# UI_Interface.net
KiCad netlist of a schematic drawn in Altium Designer
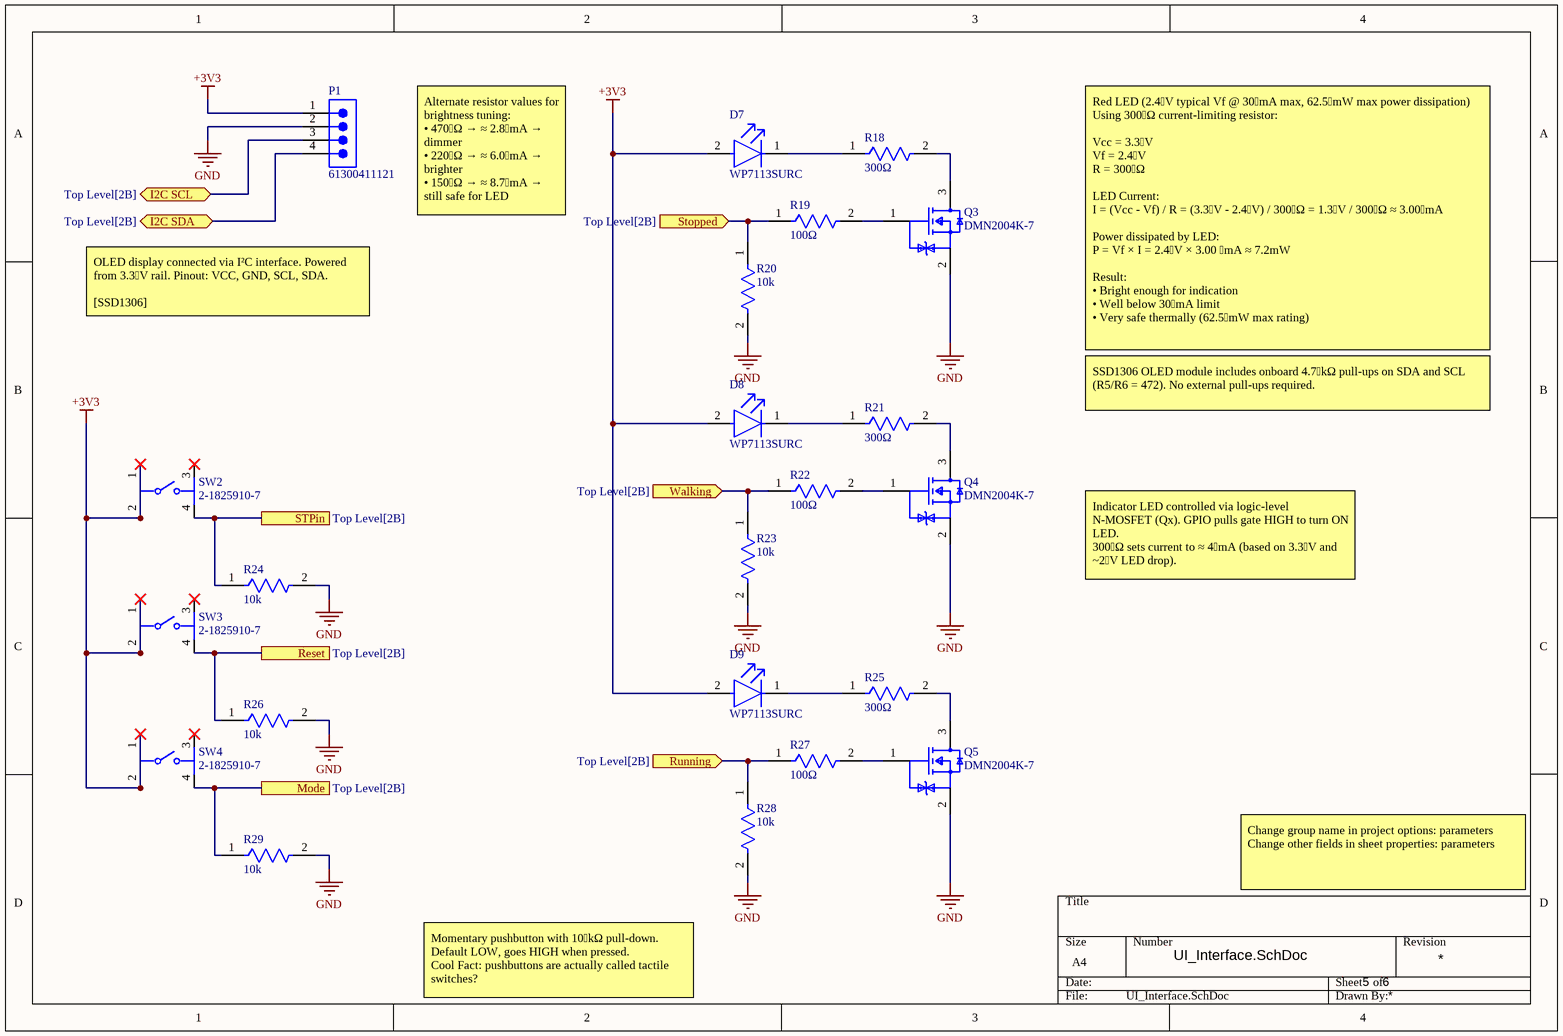
[diagram p0: UI_Interface.SchDoc]

(export (version "E")
  (design (tool "Eeschema 10.0.6"))
  (components
    (comp (ref "D7")
      (value "WP7113SURC")
      (footprint "FP-WP7113SURC-MFG")
      (description "WP7113SURC Red 5 mm 20 º Water Clear 3800 mcd 1.9 V Solid State LED Lamp - T-1 3/4")
      (libsource (lib "Altium Content Vault") (part "8706943c75ba83719d021d2fdc84c58"))
    )
    (comp (ref "D8")
      (value "WP7113SURC")
      (footprint "FP-WP7113SURC-MFG")
      (description "WP7113SURC Red 5 mm 20 º Water Clear 3800 mcd 1.9 V Solid State LED Lamp - T-1 3/4")
      (libsource (lib "Altium Content Vault") (part "8706943c75ba83719d021d2fdc84c58"))
    )
    (comp (ref "D9")
      (value "WP7113SURC")
      (footprint "FP-WP7113SURC-MFG")
      (description "WP7113SURC Red 5 mm 20 º Water Clear 3800 mcd 1.9 V Solid State LED Lamp - T-1 3/4")
      (libsource (lib "Altium Content Vault") (part "8706943c75ba83719d021d2fdc84c58"))
    )
    (comp (ref "P1")
      (value "61300411121")
      (footprint "61300411121")
      (libsource (lib "Altium Content Vault") (part "Header_Male_1R_04P"))
    )
    (comp (ref "Q3")
      (value "DMN2004K-7")
      (footprint "FP-SOT23-MFG")
      (description "MOSFET N-CH 20V 0.63A SOT23-3")
      (fields
        (field (name "OCTOPART") "https://octopart.com/dmn2004k-7-diodes+inc.-7127688")
        (field (name "MANUFACTURER") "Diodes Inc.")
      )
      (libsource (lib "Altium Content Vault") (part "6bf9a98fc5d989e2cd7172508213873"))
    )
    (comp (ref "Q4")
      (value "DMN2004K-7")
      (footprint "FP-SOT23-MFG")
      (description "MOSFET N-CH 20V 0.63A SOT23-3")
      (fields
        (field (name "OCTOPART") "https://octopart.com/dmn2004k-7-diodes+inc.-7127688")
        (field (name "MANUFACTURER") "Diodes Inc.")
      )
      (libsource (lib "Altium Content Vault") (part "6bf9a98fc5d989e2cd7172508213873"))
    )
    (comp (ref "Q5")
      (value "DMN2004K-7")
      (footprint "FP-SOT23-MFG")
      (description "MOSFET N-CH 20V 0.63A SOT23-3")
      (fields
        (field (name "OCTOPART") "https://octopart.com/dmn2004k-7-diodes+inc.-7127688")
        (field (name "MANUFACTURER") "Diodes Inc.")
      )
      (libsource (lib "Altium Content Vault") (part "6bf9a98fc5d989e2cd7172508213873"))
    )
    (comp (ref "R18")
      (value "300Ω")
      (footprint "FP-RMCF0805-IPC_B")
      (description "300Ω ±5% 0.125W 0805 Thick Film Chip Resistor AEC-Q200 compliant, RMCF0805JT300R")
      (fields (field (name "TOLERANCE") "5%"))
      (libsource (lib "Altium Content Vault") (part "1029c3af85768c4190bb7ad29bc67b5"))
    )
    (comp (ref "R19")
      (value "100Ω")
      (footprint "FP-RMCF0805-IPC_A")
      (description "100Ω ±1% 0.125W 0805 Thick Film Chip Resistor AEC-Q200 compliant, RMCF0805FT100R")
      (fields (field (name "TOLERANCE") "1%"))
      (libsource (lib "Altium Content Vault") (part "1029c3af85768c4190bb7ad29bc67b5"))
    )
    (comp (ref "R20")
      (value "10k")
      (footprint "FP-RMCF0805-MFG")
      (description "RES 10K OHM 1% 1/8W 0805, RMCF0805FT10K0")
      (fields (field (name "TOLERANCE") "1%"))
      (libsource (lib "Altium Content Vault") (part "1029c3af85768c4190bb7ad29bc67b5"))
    )
    (comp (ref "R21")
      (value "300Ω")
      (footprint "FP-RMCF0805-IPC_B")
      (description "300Ω ±5% 0.125W 0805 Thick Film Chip Resistor AEC-Q200 compliant, RMCF0805JT300R")
      (fields (field (name "TOLERANCE") "5%"))
      (libsource (lib "Altium Content Vault") (part "1029c3af85768c4190bb7ad29bc67b5"))
    )
    (comp (ref "R22")
      (value "100Ω")
      (footprint "FP-RMCF0805-IPC_A")
      (description "100Ω ±1% 0.125W 0805 Thick Film Chip Resistor AEC-Q200 compliant, RMCF0805FT100R")
      (fields (field (name "TOLERANCE") "1%"))
      (libsource (lib "Altium Content Vault") (part "1029c3af85768c4190bb7ad29bc67b5"))
    )
    (comp (ref "R23")
      (value "10k")
      (footprint "FP-RMCF0805-MFG")
      (description "RES 10K OHM 1% 1/8W 0805, RMCF0805FT10K0")
      (fields (field (name "TOLERANCE") "1%"))
      (libsource (lib "Altium Content Vault") (part "1029c3af85768c4190bb7ad29bc67b5"))
    )
    (comp (ref "R24")
      (value "10k")
      (footprint "FP-RMCF0805-MFG")
      (description "RES 10K OHM 1% 1/8W 0805, RMCF0805FT10K0")
      (fields (field (name "TOLERANCE") "1%"))
      (libsource (lib "Altium Content Vault") (part "1029c3af85768c4190bb7ad29bc67b5"))
    )
    (comp (ref "R25")
      (value "300Ω")
      (footprint "FP-RMCF0805-IPC_B")
      (description "300Ω ±5% 0.125W 0805 Thick Film Chip Resistor AEC-Q200 compliant, RMCF0805JT300R")
      (fields (field (name "TOLERANCE") "5%"))
      (libsource (lib "Altium Content Vault") (part "1029c3af85768c4190bb7ad29bc67b5"))
    )
    (comp (ref "R26")
      (value "10k")
      (footprint "FP-RMCF0805-MFG")
      (description "RES 10K OHM 1% 1/8W 0805, RMCF0805FT10K0")
      (fields (field (name "TOLERANCE") "1%"))
      (libsource (lib "Altium Content Vault") (part "1029c3af85768c4190bb7ad29bc67b5"))
    )
    (comp (ref "R27")
      (value "100Ω")
      (footprint "FP-RMCF0805-IPC_A")
      (description "100Ω ±1% 0.125W 0805 Thick Film Chip Resistor AEC-Q200 compliant, RMCF0805FT100R")
      (fields (field (name "TOLERANCE") "1%"))
      (libsource (lib "Altium Content Vault") (part "1029c3af85768c4190bb7ad29bc67b5"))
    )
    (comp (ref "R28")
      (value "10k")
      (footprint "FP-RMCF0805-MFG")
      (description "RES 10K OHM 1% 1/8W 0805, RMCF0805FT10K0")
      (fields (field (name "TOLERANCE") "1%"))
      (libsource (lib "Altium Content Vault") (part "1029c3af85768c4190bb7ad29bc67b5"))
    )
    (comp (ref "R29")
      (value "10k")
      (footprint "FP-RMCF0805-MFG")
      (description "RES 10K OHM 1% 1/8W 0805, RMCF0805FT10K0")
      (fields (field (name "TOLERANCE") "1%"))
      (libsource (lib "Altium Content Vault") (part "1029c3af85768c4190bb7ad29bc67b5"))
    )
    (comp (ref "SW2")
      (value "2-1825910-7")
      (footprint "FP-2-1825910-7-MFG")
      (description "SWITCH TACTILE SPST-NO 0.05A 24V")
      (fields
        (field (name "MANUFACTURER") "TE Connectivity")
        (field (name "OCTOPART") "https://octopart.com/2-1825910-7-te+connectivity-42270510")
      )
      (libsource (lib "Altium Content Vault") (part "b8895f3f4cefb76e1819d2863dba89b"))
    )
    (comp (ref "SW3")
      (value "2-1825910-7")
      (footprint "FP-2-1825910-7-MFG")
      (description "SWITCH TACTILE SPST-NO 0.05A 24V")
      (fields
        (field (name "MANUFACTURER") "TE Connectivity")
        (field (name "OCTOPART") "https://octopart.com/2-1825910-7-te+connectivity-42270510")
      )
      (libsource (lib "Altium Content Vault") (part "b8895f3f4cefb76e1819d2863dba89b"))
    )
    (comp (ref "SW4")
      (value "2-1825910-7")
      (footprint "FP-2-1825910-7-MFG")
      (description "SWITCH TACTILE SPST-NO 0.05A 24V")
      (fields
        (field (name "MANUFACTURER") "TE Connectivity")
        (field (name "OCTOPART") "https://octopart.com/2-1825910-7-te+connectivity-42270510")
      )
      (libsource (lib "Altium Content Vault") (part "b8895f3f4cefb76e1819d2863dba89b"))
    )
  )
  (nets
    (net (code "1") (name "+3V3") (class "Default")
      (node (ref "D7") (pin "2") (pinfunction "A_2") (pintype "passive"))
      (node (ref "D8") (pin "2") (pinfunction "A_2") (pintype "passive"))
      (node (ref "D9") (pin "2") (pinfunction "A_2") (pintype "passive"))
      (node (ref "P1") (pin "1") (pinfunction "1_1") (pintype "passive"))
      (node (ref "SW2") (pin "1") (pinfunction "1_1") (pintype "passive"))
      (node (ref "SW2") (pin "2") (pinfunction "2_2") (pintype "passive"))
      (node (ref "SW3") (pin "1") (pinfunction "1_1") (pintype "passive"))
      (node (ref "SW3") (pin "2") (pinfunction "2_2") (pintype "passive"))
      (node (ref "SW4") (pin "1") (pinfunction "1_1") (pintype "passive"))
      (node (ref "SW4") (pin "2") (pinfunction "2_2") (pintype "passive"))
    )
    (net (code "2") (name "/I2C SCL") (class "Default")
      (node (ref "P1") (pin "3") (pinfunction "3_3") (pintype "passive"))
    )
    (net (code "3") (name "/I2C SDA") (class "Default")
      (node (ref "P1") (pin "4") (pinfunction "4_4") (pintype "passive"))
    )
    (net (code "4") (name "/Mode") (class "Default")
      (node (ref "R29") (pin "1") (pinfunction "1_1") (pintype "passive"))
      (node (ref "SW4") (pin "4") (pinfunction "4_4") (pintype "passive"))
    )
    (net (code "5") (name "/Reset") (class "Default")
      (node (ref "R26") (pin "1") (pinfunction "1_1") (pintype "passive"))
      (node (ref "SW3") (pin "4") (pinfunction "4_4") (pintype "passive"))
    )
    (net (code "6") (name "/Running") (class "Default")
      (node (ref "R27") (pin "1") (pinfunction "1_1") (pintype "passive"))
      (node (ref "R28") (pin "1") (pinfunction "1_1") (pintype "passive"))
    )
    (net (code "7") (name "/STPin") (class "Default")
      (node (ref "R24") (pin "1") (pinfunction "1_1") (pintype "passive"))
      (node (ref "SW2") (pin "4") (pinfunction "4_4") (pintype "passive"))
    )
    (net (code "8") (name "/Stopped") (class "Default")
      (node (ref "R19") (pin "1") (pinfunction "1_1") (pintype "passive"))
      (node (ref "R20") (pin "1") (pinfunction "1_1") (pintype "passive"))
    )
    (net (code "9") (name "/Walking") (class "Default")
      (node (ref "R22") (pin "1") (pinfunction "1_1") (pintype "passive"))
      (node (ref "R23") (pin "1") (pinfunction "1_1") (pintype "passive"))
    )
    (net (code "10") (name "GND") (class "Default")
      (node (ref "P1") (pin "2") (pinfunction "2_2") (pintype "passive"))
      (node (ref "Q3") (pin "2") (pinfunction "S_2") (pintype "passive"))
      (node (ref "Q4") (pin "2") (pinfunction "S_2") (pintype "passive"))
      (node (ref "Q5") (pin "2") (pinfunction "S_2") (pintype "passive"))
      (node (ref "R20") (pin "2") (pinfunction "2_2") (pintype "passive"))
      (node (ref "R23") (pin "2") (pinfunction "2_2") (pintype "passive"))
      (node (ref "R24") (pin "2") (pinfunction "2_2") (pintype "passive"))
      (node (ref "R26") (pin "2") (pinfunction "2_2") (pintype "passive"))
      (node (ref "R28") (pin "2") (pinfunction "2_2") (pintype "passive"))
      (node (ref "R29") (pin "2") (pinfunction "2_2") (pintype "passive"))
    )
    (net (code "11") (name "Net-(D7-C)") (class "Default")
      (node (ref "D7") (pin "1") (pinfunction "C_1") (pintype "passive"))
      (node (ref "R18") (pin "1") (pinfunction "1_1") (pintype "passive"))
    )
    (net (code "12") (name "Net-(D8-C)") (class "Default")
      (node (ref "D8") (pin "1") (pinfunction "C_1") (pintype "passive"))
      (node (ref "R21") (pin "1") (pinfunction "1_1") (pintype "passive"))
    )
    (net (code "13") (name "Net-(D9-C)") (class "Default")
      (node (ref "D9") (pin "1") (pinfunction "C_1") (pintype "passive"))
      (node (ref "R25") (pin "1") (pinfunction "1_1") (pintype "passive"))
    )
    (net (code "14") (name "Net-(Q3-D)") (class "Default")
      (node (ref "Q3") (pin "3") (pinfunction "D_3") (pintype "passive"))
      (node (ref "R18") (pin "2") (pinfunction "2_2") (pintype "passive"))
    )
    (net (code "15") (name "Net-(Q3-G)") (class "Default")
      (node (ref "Q3") (pin "1") (pinfunction "G_1") (pintype "passive"))
      (node (ref "R19") (pin "2") (pinfunction "2_2") (pintype "passive"))
    )
    (net (code "16") (name "Net-(Q4-D)") (class "Default")
      (node (ref "Q4") (pin "3") (pinfunction "D_3") (pintype "passive"))
      (node (ref "R21") (pin "2") (pinfunction "2_2") (pintype "passive"))
    )
    (net (code "17") (name "Net-(Q4-G)") (class "Default")
      (node (ref "Q4") (pin "1") (pinfunction "G_1") (pintype "passive"))
      (node (ref "R22") (pin "2") (pinfunction "2_2") (pintype "passive"))
    )
    (net (code "18") (name "Net-(Q5-D)") (class "Default")
      (node (ref "Q5") (pin "3") (pinfunction "D_3") (pintype "passive"))
      (node (ref "R25") (pin "2") (pinfunction "2_2") (pintype "passive"))
    )
    (net (code "19") (name "Net-(Q5-G)") (class "Default")
      (node (ref "Q5") (pin "1") (pinfunction "G_1") (pintype "passive"))
      (node (ref "R27") (pin "2") (pinfunction "2_2") (pintype "passive"))
    )
    (net (code "20") (name "unconnected-(SW2-Pad3)") (class "Default")
      (node (ref "SW2") (pin "3") (pinfunction "3_3") (pintype "passive+no_connect"))
    )
    (net (code "21") (name "unconnected-(SW3-Pad3)") (class "Default")
      (node (ref "SW3") (pin "3") (pinfunction "3_3") (pintype "passive+no_connect"))
    )
    (net (code "22") (name "unconnected-(SW4-Pad3)") (class "Default")
      (node (ref "SW4") (pin "3") (pinfunction "3_3") (pintype "passive+no_connect"))
    )
  )
)
